# pcb-txcm.net
KiCad netlist of a schematic drawn in EAGLE
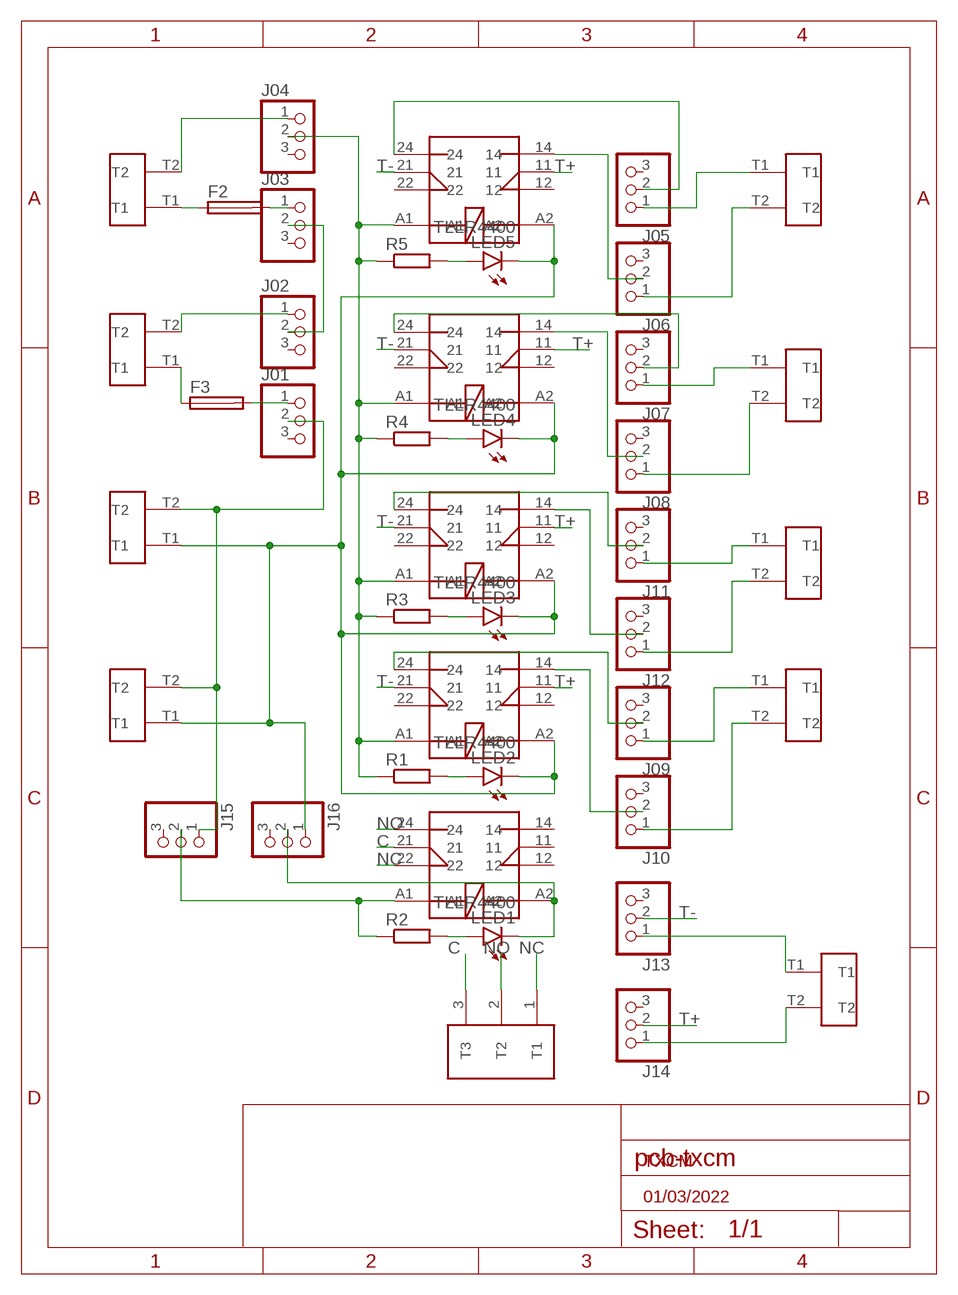
[diagram p0: schematic, sheet 1]

(export (version "E")
  (design (tool "Eeschema 10.0.6"))
  (components
    (comp (ref "F2")
      (value "SH22,5A")
      (footprint "eagle-import:SH22,5A")
      (fields (field (name "MPN") "0031.7701.11"))
      (libsource (lib "eagle-import") (part "SH22,5A"))
    )
    (comp (ref "F3")
      (value "SH22,5A")
      (footprint "eagle-import:SH22,5A")
      (fields (field (name "MPN") "0031.7701.11"))
      (libsource (lib "eagle-import") (part "SH22,5A"))
    )
    (comp (ref "J01")
      (value "PINHD-1X3")
      (footprint "eagle-import:1X03")
      (libsource (lib "eagle-import") (part "PINHD-1X3"))
    )
    (comp (ref "J02")
      (value "PINHD-1X3")
      (footprint "eagle-import:1X03")
      (libsource (lib "eagle-import") (part "PINHD-1X3"))
    )
    (comp (ref "J03")
      (value "PINHD-1X3")
      (footprint "eagle-import:1X03")
      (libsource (lib "eagle-import") (part "PINHD-1X3"))
    )
    (comp (ref "J04")
      (value "PINHD-1X3")
      (footprint "eagle-import:1X03")
      (libsource (lib "eagle-import") (part "PINHD-1X3"))
    )
    (comp (ref "J05")
      (value "PINHD-1X3")
      (footprint "eagle-import:1X03")
      (libsource (lib "eagle-import") (part "PINHD-1X3"))
    )
    (comp (ref "J06")
      (value "PINHD-1X3")
      (footprint "eagle-import:1X03")
      (libsource (lib "eagle-import") (part "PINHD-1X3"))
    )
    (comp (ref "J07")
      (value "PINHD-1X3")
      (footprint "eagle-import:1X03")
      (libsource (lib "eagle-import") (part "PINHD-1X3"))
    )
    (comp (ref "J08")
      (value "PINHD-1X3")
      (footprint "eagle-import:1X03")
      (libsource (lib "eagle-import") (part "PINHD-1X3"))
    )
    (comp (ref "J09")
      (value "PINHD-1X3")
      (footprint "eagle-import:1X03")
      (libsource (lib "eagle-import") (part "PINHD-1X3"))
    )
    (comp (ref "J10")
      (value "PINHD-1X3")
      (footprint "eagle-import:1X03")
      (libsource (lib "eagle-import") (part "PINHD-1X3"))
    )
    (comp (ref "J11")
      (value "PINHD-1X3")
      (footprint "eagle-import:1X03")
      (libsource (lib "eagle-import") (part "PINHD-1X3"))
    )
    (comp (ref "J12")
      (value "PINHD-1X3")
      (footprint "eagle-import:1X03")
      (libsource (lib "eagle-import") (part "PINHD-1X3"))
    )
    (comp (ref "J13")
      (value "PINHD-1X3")
      (footprint "eagle-import:1X03")
      (libsource (lib "eagle-import") (part "PINHD-1X3"))
    )
    (comp (ref "J14")
      (value "PINHD-1X3")
      (footprint "eagle-import:1X03")
      (libsource (lib "eagle-import") (part "PINHD-1X3"))
    )
    (comp (ref "J15")
      (value "PINHD-1X3")
      (footprint "eagle-import:1X03")
      (libsource (lib "eagle-import") (part "PINHD-1X3"))
    )
    (comp (ref "J16")
      (value "PINHD-1X3")
      (footprint "eagle-import:1X03")
      (libsource (lib "eagle-import") (part "PINHD-1X3"))
    )
    (comp (ref "LED1")
      (value "TLLR4400")
      (footprint "eagle-import:LED3MM")
      (fields (field (name "MF") "VISHAY SEMICONDUCTOR"))
      (libsource (lib "eagle-import") (part "TLLR4400"))
    )
    (comp (ref "LED2")
      (value "TLLR4400")
      (footprint "eagle-import:LED3MM")
      (fields (field (name "MF") "VISHAY SEMICONDUCTOR"))
      (libsource (lib "eagle-import") (part "TLLR4400"))
    )
    (comp (ref "LED3")
      (value "TLLR4400")
      (footprint "eagle-import:LED3MM")
      (fields (field (name "MF") "VISHAY SEMICONDUCTOR"))
      (libsource (lib "eagle-import") (part "TLLR4400"))
    )
    (comp (ref "LED4")
      (value "TLLR4400")
      (footprint "eagle-import:LED3MM")
      (fields (field (name "MF") "VISHAY SEMICONDUCTOR"))
      (libsource (lib "eagle-import") (part "TLLR4400"))
    )
    (comp (ref "LED5")
      (value "TLLR4400")
      (footprint "eagle-import:LED3MM")
      (fields (field (name "MF") "VISHAY SEMICONDUCTOR"))
      (libsource (lib "eagle-import") (part "TLLR4400"))
    )
    (comp (ref "R1")
      (value "R-EU_0309/12")
      (footprint "eagle-import:0309_12")
      (libsource (lib "eagle-import") (part "R-EU_0309/12"))
    )
    (comp (ref "R2")
      (value "R-EU_0309/12")
      (footprint "eagle-import:0309_12")
      (libsource (lib "eagle-import") (part "R-EU_0309/12"))
    )
    (comp (ref "R3")
      (value "R-EU_0309/12")
      (footprint "eagle-import:0309_12")
      (libsource (lib "eagle-import") (part "R-EU_0309/12"))
    )
    (comp (ref "R4")
      (value "R-EU_0309/12")
      (footprint "eagle-import:0309_12")
      (libsource (lib "eagle-import") (part "R-EU_0309/12"))
    )
    (comp (ref "R5")
      (value "R-EU_0309/12")
      (footprint "eagle-import:0309_12")
      (libsource (lib "eagle-import") (part "R-EU_0309/12"))
    )
    (comp (ref "RSB2A080ED1")
      (value "RSB2A080ED")
      (footprint "eagle-import:RSB2A080ED")
      (libsource (lib "eagle-import") (part "RSB2A080ED"))
    )
    (comp (ref "RSB2A080ED2")
      (value "RSB2A080ED")
      (footprint "eagle-import:RSB2A080ED")
      (libsource (lib "eagle-import") (part "RSB2A080ED"))
    )
    (comp (ref "RSB2A080ED3")
      (value "RSB2A080ED")
      (footprint "eagle-import:RSB2A080ED")
      (libsource (lib "eagle-import") (part "RSB2A080ED"))
    )
    (comp (ref "RSB2A080ED4")
      (value "RSB2A080ED")
      (footprint "eagle-import:RSB2A080ED")
      (libsource (lib "eagle-import") (part "RSB2A080ED"))
    )
    (comp (ref "RSB2A080ED5")
      (value "RSB2A080ED")
      (footprint "eagle-import:RSB2A080ED")
      (libsource (lib "eagle-import") (part "RSB2A080ED"))
    )
    (comp (ref "TB7.1")
      (value "TB7.62")
      (footprint "eagle-import:TB7.62")
      (libsource (lib "eagle-import") (part "TB7.62"))
    )
    (comp (ref "TB7.2")
      (value "TB7.62")
      (footprint "eagle-import:TB7.62")
      (libsource (lib "eagle-import") (part "TB7.62"))
    )
    (comp (ref "TB7.3")
      (value "TB7.62")
      (footprint "eagle-import:TB7.62")
      (libsource (lib "eagle-import") (part "TB7.62"))
    )
    (comp (ref "TB7.4")
      (value "TB7.62")
      (footprint "eagle-import:TB7.62")
      (libsource (lib "eagle-import") (part "TB7.62"))
    )
    (comp (ref "TB7.6")
      (value "TB7.62")
      (footprint "eagle-import:TB7.62")
      (libsource (lib "eagle-import") (part "TB7.62"))
    )
    (comp (ref "TB7.7")
      (value "TB7.62")
      (footprint "eagle-import:TB7.62")
      (libsource (lib "eagle-import") (part "TB7.62"))
    )
    (comp (ref "TB7.8")
      (value "TB7.62")
      (footprint "eagle-import:TB7.62")
      (libsource (lib "eagle-import") (part "TB7.62"))
    )
    (comp (ref "TB7.9")
      (value "TB7.62")
      (footprint "eagle-import:TB7.62")
      (libsource (lib "eagle-import") (part "TB7.62"))
    )
    (comp (ref "TB7.10")
      (value "TB7.62")
      (footprint "eagle-import:TB7.62")
      (libsource (lib "eagle-import") (part "TB7.62"))
    )
    (comp (ref "TB7.62-3P1")
      (value "TB7.62-3P")
      (footprint "eagle-import:TB7.62-3P")
      (libsource (lib "eagle-import") (part "TB7.62-3P"))
    )
  )
  (nets
    (net (code "1") (name "/C") (class "Default")
      (node (ref "RSB2A080ED5") (pin "21") (pinfunction "21_21") (pintype "bidirectional"))
      (node (ref "TB7.62-3P1") (pin "3") (pinfunction "T3_3") (pintype "bidirectional"))
    )
    (net (code "2") (name "/NC") (class "Default")
      (node (ref "RSB2A080ED5") (pin "22") (pinfunction "22_22") (pintype "bidirectional"))
      (node (ref "TB7.62-3P1") (pin "1") (pinfunction "T1_1") (pintype "bidirectional"))
    )
    (net (code "3") (name "/NO") (class "Default")
      (node (ref "RSB2A080ED5") (pin "24") (pinfunction "24_24") (pintype "bidirectional"))
      (node (ref "TB7.62-3P1") (pin "2") (pinfunction "T2_2") (pintype "bidirectional"))
    )
    (net (code "4") (name "/T+") (class "Default")
      (node (ref "J14") (pin "2") (pinfunction "2_2") (pintype "passive"))
      (node (ref "RSB2A080ED1") (pin "11") (pinfunction "11_11") (pintype "bidirectional"))
      (node (ref "RSB2A080ED2") (pin "11") (pinfunction "11_11") (pintype "bidirectional"))
      (node (ref "RSB2A080ED3") (pin "11") (pinfunction "11_11") (pintype "bidirectional"))
      (node (ref "RSB2A080ED4") (pin "11") (pinfunction "11_11") (pintype "bidirectional"))
    )
    (net (code "5") (name "/T-") (class "Default")
      (node (ref "J13") (pin "2") (pinfunction "2_2") (pintype "passive"))
      (node (ref "RSB2A080ED1") (pin "21") (pinfunction "21_21") (pintype "bidirectional"))
      (node (ref "RSB2A080ED2") (pin "21") (pinfunction "21_21") (pintype "bidirectional"))
      (node (ref "RSB2A080ED3") (pin "21") (pinfunction "21_21") (pintype "bidirectional"))
      (node (ref "RSB2A080ED4") (pin "21") (pinfunction "21_21") (pintype "bidirectional"))
    )
    (net (code "6") (name "Net-(F2-Pad1)") (class "Default")
      (node (ref "F2") (pin "1") (pinfunction "1_1") (pintype "passive"))
      (node (ref "TB7.1") (pin "T1") (pinfunction "T1_T1") (pintype "bidirectional"))
    )
    (net (code "7") (name "Net-(F2-Pad2)") (class "Default")
      (node (ref "F2") (pin "2") (pinfunction "2_2") (pintype "passive"))
      (node (ref "J03") (pin "1") (pinfunction "1_1") (pintype "passive"))
    )
    (net (code "8") (name "Net-(F3-Pad1)") (class "Default")
      (node (ref "F3") (pin "1") (pinfunction "1_1") (pintype "passive"))
      (node (ref "TB7.2") (pin "T1") (pinfunction "T1_T1") (pintype "bidirectional"))
    )
    (net (code "9") (name "Net-(F3-Pad2)") (class "Default")
      (node (ref "F3") (pin "2") (pinfunction "2_2") (pintype "passive"))
      (node (ref "J01") (pin "1") (pinfunction "1_1") (pintype "passive"))
    )
    (net (code "10") (name "Net-(J01-Pad2)") (class "Default")
      (node (ref "J01") (pin "2") (pinfunction "2_2") (pintype "passive"))
      (node (ref "J15") (pin "1") (pinfunction "1_1") (pintype "passive"))
      (node (ref "TB7.3") (pin "T2") (pinfunction "T2_T2") (pintype "bidirectional"))
      (node (ref "TB7.4") (pin "T2") (pinfunction "T2_T2") (pintype "bidirectional"))
    )
    (net (code "11") (name "Net-(J02-Pad1)") (class "Default")
      (node (ref "J02") (pin "1") (pinfunction "1_1") (pintype "passive"))
      (node (ref "TB7.2") (pin "T2") (pinfunction "T2_T2") (pintype "bidirectional"))
    )
    (net (code "12") (name "Net-(J02-Pad2)") (class "Default")
      (node (ref "J02") (pin "2") (pinfunction "2_2") (pintype "passive"))
      (node (ref "J03") (pin "2") (pinfunction "2_2") (pintype "passive"))
    )
    (net (code "13") (name "Net-(J04-Pad1)") (class "Default")
      (node (ref "J04") (pin "1") (pinfunction "1_1") (pintype "passive"))
      (node (ref "TB7.1") (pin "T2") (pinfunction "T2_T2") (pintype "bidirectional"))
    )
    (net (code "14") (name "Net-(J04-Pad2)") (class "Default")
      (node (ref "J04") (pin "2") (pinfunction "2_2") (pintype "passive"))
      (node (ref "R1") (pin "1") (pinfunction "1_1") (pintype "passive"))
      (node (ref "R3") (pin "1") (pinfunction "1_1") (pintype "passive"))
      (node (ref "R4") (pin "1") (pinfunction "1_1") (pintype "passive"))
      (node (ref "R5") (pin "1") (pinfunction "1_1") (pintype "passive"))
      (node (ref "RSB2A080ED1") (pin "A1") (pinfunction "A1_A1") (pintype "bidirectional"))
      (node (ref "RSB2A080ED2") (pin "A1") (pinfunction "A1_A1") (pintype "bidirectional"))
      (node (ref "RSB2A080ED3") (pin "A1") (pinfunction "A1_A1") (pintype "bidirectional"))
      (node (ref "RSB2A080ED4") (pin "A1") (pinfunction "A1_A1") (pintype "bidirectional"))
    )
    (net (code "15") (name "Net-(J05-Pad1)") (class "Default")
      (node (ref "J05") (pin "1") (pinfunction "1_1") (pintype "passive"))
      (node (ref "TB7.6") (pin "T1") (pinfunction "T1_T1") (pintype "bidirectional"))
    )
    (net (code "16") (name "Net-(J05-Pad2)") (class "Default")
      (node (ref "J05") (pin "2") (pinfunction "2_2") (pintype "passive"))
      (node (ref "RSB2A080ED1") (pin "24") (pinfunction "24_24") (pintype "bidirectional"))
    )
    (net (code "17") (name "Net-(J06-Pad1)") (class "Default")
      (node (ref "J06") (pin "1") (pinfunction "1_1") (pintype "passive"))
      (node (ref "TB7.6") (pin "T2") (pinfunction "T2_T2") (pintype "bidirectional"))
    )
    (net (code "18") (name "Net-(J06-Pad2)") (class "Default")
      (node (ref "J06") (pin "2") (pinfunction "2_2") (pintype "passive"))
      (node (ref "RSB2A080ED1") (pin "14") (pinfunction "14_14") (pintype "bidirectional"))
    )
    (net (code "19") (name "Net-(J07-Pad1)") (class "Default")
      (node (ref "J07") (pin "1") (pinfunction "1_1") (pintype "passive"))
      (node (ref "TB7.7") (pin "T1") (pinfunction "T1_T1") (pintype "bidirectional"))
    )
    (net (code "20") (name "Net-(J07-Pad2)") (class "Default")
      (node (ref "J07") (pin "2") (pinfunction "2_2") (pintype "passive"))
      (node (ref "RSB2A080ED2") (pin "24") (pinfunction "24_24") (pintype "bidirectional"))
    )
    (net (code "21") (name "Net-(J08-Pad1)") (class "Default")
      (node (ref "J08") (pin "1") (pinfunction "1_1") (pintype "passive"))
      (node (ref "TB7.7") (pin "T2") (pinfunction "T2_T2") (pintype "bidirectional"))
    )
    (net (code "22") (name "Net-(J08-Pad2)") (class "Default")
      (node (ref "J08") (pin "2") (pinfunction "2_2") (pintype "passive"))
      (node (ref "RSB2A080ED2") (pin "14") (pinfunction "14_14") (pintype "bidirectional"))
    )
    (net (code "23") (name "Net-(J09-Pad1)") (class "Default")
      (node (ref "J09") (pin "1") (pinfunction "1_1") (pintype "passive"))
      (node (ref "TB7.9") (pin "T1") (pinfunction "T1_T1") (pintype "bidirectional"))
    )
    (net (code "24") (name "Net-(J09-Pad2)") (class "Default")
      (node (ref "J09") (pin "2") (pinfunction "2_2") (pintype "passive"))
      (node (ref "RSB2A080ED4") (pin "24") (pinfunction "24_24") (pintype "bidirectional"))
    )
    (net (code "25") (name "Net-(J10-Pad1)") (class "Default")
      (node (ref "J10") (pin "1") (pinfunction "1_1") (pintype "passive"))
      (node (ref "TB7.9") (pin "T2") (pinfunction "T2_T2") (pintype "bidirectional"))
    )
    (net (code "26") (name "Net-(J10-Pad2)") (class "Default")
      (node (ref "J10") (pin "2") (pinfunction "2_2") (pintype "passive"))
      (node (ref "RSB2A080ED4") (pin "14") (pinfunction "14_14") (pintype "bidirectional"))
    )
    (net (code "27") (name "Net-(J11-Pad1)") (class "Default")
      (node (ref "J11") (pin "1") (pinfunction "1_1") (pintype "passive"))
      (node (ref "TB7.8") (pin "T1") (pinfunction "T1_T1") (pintype "bidirectional"))
    )
    (net (code "28") (name "Net-(J11-Pad2)") (class "Default")
      (node (ref "J11") (pin "2") (pinfunction "2_2") (pintype "passive"))
      (node (ref "RSB2A080ED3") (pin "24") (pinfunction "24_24") (pintype "bidirectional"))
    )
    (net (code "29") (name "Net-(J12-Pad1)") (class "Default")
      (node (ref "J12") (pin "1") (pinfunction "1_1") (pintype "passive"))
      (node (ref "TB7.8") (pin "T2") (pinfunction "T2_T2") (pintype "bidirectional"))
    )
    (net (code "30") (name "Net-(J12-Pad2)") (class "Default")
      (node (ref "J12") (pin "2") (pinfunction "2_2") (pintype "passive"))
      (node (ref "RSB2A080ED3") (pin "14") (pinfunction "14_14") (pintype "bidirectional"))
    )
    (net (code "31") (name "Net-(J13-Pad1)") (class "Default")
      (node (ref "J13") (pin "1") (pinfunction "1_1") (pintype "passive"))
      (node (ref "TB7.10") (pin "T1") (pinfunction "T1_T1") (pintype "bidirectional"))
    )
    (net (code "32") (name "Net-(J14-Pad1)") (class "Default")
      (node (ref "J14") (pin "1") (pinfunction "1_1") (pintype "passive"))
      (node (ref "TB7.10") (pin "T2") (pinfunction "T2_T2") (pintype "bidirectional"))
    )
    (net (code "33") (name "Net-(J15-Pad2)") (class "Default")
      (node (ref "J15") (pin "2") (pinfunction "2_2") (pintype "passive"))
      (node (ref "R2") (pin "1") (pinfunction "1_1") (pintype "passive"))
      (node (ref "RSB2A080ED5") (pin "A1") (pinfunction "A1_A1") (pintype "bidirectional"))
    )
    (net (code "34") (name "Net-(LED1-C)") (class "Default")
      (node (ref "J16") (pin "2") (pinfunction "2_2") (pintype "passive"))
      (node (ref "LED1") (pin "K") (pinfunction "C_K") (pintype "passive"))
      (node (ref "RSB2A080ED5") (pin "A2") (pinfunction "A2_A2") (pintype "bidirectional"))
    )
    (net (code "35") (name "Net-(LED1-PadA)") (class "Default")
      (node (ref "LED1") (pin "A") (pinfunction "A_A") (pintype "passive"))
      (node (ref "R2") (pin "2") (pinfunction "2_2") (pintype "passive"))
    )
    (net (code "36") (name "Net-(LED2-C)") (class "Default")
      (node (ref "J16") (pin "1") (pinfunction "1_1") (pintype "passive"))
      (node (ref "LED2") (pin "K") (pinfunction "C_K") (pintype "passive"))
      (node (ref "LED3") (pin "K") (pinfunction "C_K") (pintype "passive"))
      (node (ref "LED4") (pin "K") (pinfunction "C_K") (pintype "passive"))
      (node (ref "LED5") (pin "K") (pinfunction "C_K") (pintype "passive"))
      (node (ref "RSB2A080ED1") (pin "A2") (pinfunction "A2_A2") (pintype "bidirectional"))
      (node (ref "RSB2A080ED2") (pin "A2") (pinfunction "A2_A2") (pintype "bidirectional"))
      (node (ref "RSB2A080ED3") (pin "A2") (pinfunction "A2_A2") (pintype "bidirectional"))
      (node (ref "RSB2A080ED4") (pin "A2") (pinfunction "A2_A2") (pintype "bidirectional"))
      (node (ref "TB7.3") (pin "T1") (pinfunction "T1_T1") (pintype "bidirectional"))
      (node (ref "TB7.4") (pin "T1") (pinfunction "T1_T1") (pintype "bidirectional"))
    )
    (net (code "37") (name "Net-(LED2-PadA)") (class "Default")
      (node (ref "LED2") (pin "A") (pinfunction "A_A") (pintype "passive"))
      (node (ref "R1") (pin "2") (pinfunction "2_2") (pintype "passive"))
    )
    (net (code "38") (name "Net-(LED3-PadA)") (class "Default")
      (node (ref "LED3") (pin "A") (pinfunction "A_A") (pintype "passive"))
      (node (ref "R3") (pin "2") (pinfunction "2_2") (pintype "passive"))
    )
    (net (code "39") (name "Net-(LED4-PadA)") (class "Default")
      (node (ref "LED4") (pin "A") (pinfunction "A_A") (pintype "passive"))
      (node (ref "R4") (pin "2") (pinfunction "2_2") (pintype "passive"))
    )
    (net (code "40") (name "Net-(LED5-PadA)") (class "Default")
      (node (ref "LED5") (pin "A") (pinfunction "A_A") (pintype "passive"))
      (node (ref "R5") (pin "2") (pinfunction "2_2") (pintype "passive"))
    )
    (net (code "41") (name "unconnected-(J01-Pad3)") (class "Default")
      (node (ref "J01") (pin "3") (pinfunction "3_3") (pintype "passive"))
    )
    (net (code "42") (name "unconnected-(J02-Pad3)") (class "Default")
      (node (ref "J02") (pin "3") (pinfunction "3_3") (pintype "passive"))
    )
    (net (code "43") (name "unconnected-(J03-Pad3)") (class "Default")
      (node (ref "J03") (pin "3") (pinfunction "3_3") (pintype "passive"))
    )
    (net (code "44") (name "unconnected-(J04-Pad3)") (class "Default")
      (node (ref "J04") (pin "3") (pinfunction "3_3") (pintype "passive"))
    )
    (net (code "45") (name "unconnected-(J05-Pad3)") (class "Default")
      (node (ref "J05") (pin "3") (pinfunction "3_3") (pintype "passive"))
    )
    (net (code "46") (name "unconnected-(J06-Pad3)") (class "Default")
      (node (ref "J06") (pin "3") (pinfunction "3_3") (pintype "passive"))
    )
    (net (code "47") (name "unconnected-(J07-Pad3)") (class "Default")
      (node (ref "J07") (pin "3") (pinfunction "3_3") (pintype "passive"))
    )
    (net (code "48") (name "unconnected-(J08-Pad3)") (class "Default")
      (node (ref "J08") (pin "3") (pinfunction "3_3") (pintype "passive"))
    )
    (net (code "49") (name "unconnected-(J09-Pad3)") (class "Default")
      (node (ref "J09") (pin "3") (pinfunction "3_3") (pintype "passive"))
    )
    (net (code "50") (name "unconnected-(J10-Pad3)") (class "Default")
      (node (ref "J10") (pin "3") (pinfunction "3_3") (pintype "passive"))
    )
    (net (code "51") (name "unconnected-(J11-Pad3)") (class "Default")
      (node (ref "J11") (pin "3") (pinfunction "3_3") (pintype "passive"))
    )
    (net (code "52") (name "unconnected-(J12-Pad3)") (class "Default")
      (node (ref "J12") (pin "3") (pinfunction "3_3") (pintype "passive"))
    )
    (net (code "53") (name "unconnected-(J13-Pad3)") (class "Default")
      (node (ref "J13") (pin "3") (pinfunction "3_3") (pintype "passive"))
    )
    (net (code "54") (name "unconnected-(J14-Pad3)") (class "Default")
      (node (ref "J14") (pin "3") (pinfunction "3_3") (pintype "passive"))
    )
    (net (code "55") (name "unconnected-(J15-Pad3)") (class "Default")
      (node (ref "J15") (pin "3") (pinfunction "3_3") (pintype "passive"))
    )
    (net (code "56") (name "unconnected-(J16-Pad3)") (class "Default")
      (node (ref "J16") (pin "3") (pinfunction "3_3") (pintype "passive"))
    )
    (net (code "57") (name "unconnected-(RSB2A080ED1-Pad12)") (class "Default")
      (node (ref "RSB2A080ED1") (pin "12") (pinfunction "12_12") (pintype "bidirectional"))
    )
    (net (code "58") (name "unconnected-(RSB2A080ED1-Pad22)") (class "Default")
      (node (ref "RSB2A080ED1") (pin "22") (pinfunction "22_22") (pintype "bidirectional"))
    )
    (net (code "59") (name "unconnected-(RSB2A080ED2-Pad12)") (class "Default")
      (node (ref "RSB2A080ED2") (pin "12") (pinfunction "12_12") (pintype "bidirectional"))
    )
    (net (code "60") (name "unconnected-(RSB2A080ED2-Pad22)") (class "Default")
      (node (ref "RSB2A080ED2") (pin "22") (pinfunction "22_22") (pintype "bidirectional"))
    )
    (net (code "61") (name "unconnected-(RSB2A080ED3-Pad12)") (class "Default")
      (node (ref "RSB2A080ED3") (pin "12") (pinfunction "12_12") (pintype "bidirectional"))
    )
    (net (code "62") (name "unconnected-(RSB2A080ED3-Pad22)") (class "Default")
      (node (ref "RSB2A080ED3") (pin "22") (pinfunction "22_22") (pintype "bidirectional"))
    )
    (net (code "63") (name "unconnected-(RSB2A080ED4-Pad12)") (class "Default")
      (node (ref "RSB2A080ED4") (pin "12") (pinfunction "12_12") (pintype "bidirectional"))
    )
    (net (code "64") (name "unconnected-(RSB2A080ED4-Pad22)") (class "Default")
      (node (ref "RSB2A080ED4") (pin "22") (pinfunction "22_22") (pintype "bidirectional"))
    )
    (net (code "65") (name "unconnected-(RSB2A080ED5-Pad11)") (class "Default")
      (node (ref "RSB2A080ED5") (pin "11") (pinfunction "11_11") (pintype "bidirectional"))
    )
    (net (code "66") (name "unconnected-(RSB2A080ED5-Pad12)") (class "Default")
      (node (ref "RSB2A080ED5") (pin "12") (pinfunction "12_12") (pintype "bidirectional"))
    )
    (net (code "67") (name "unconnected-(RSB2A080ED5-Pad14)") (class "Default")
      (node (ref "RSB2A080ED5") (pin "14") (pinfunction "14_14") (pintype "bidirectional"))
    )
  )
)
